# bms-slave-magnetics.net
KiCad netlist of a schematic drawn in Altium Designer
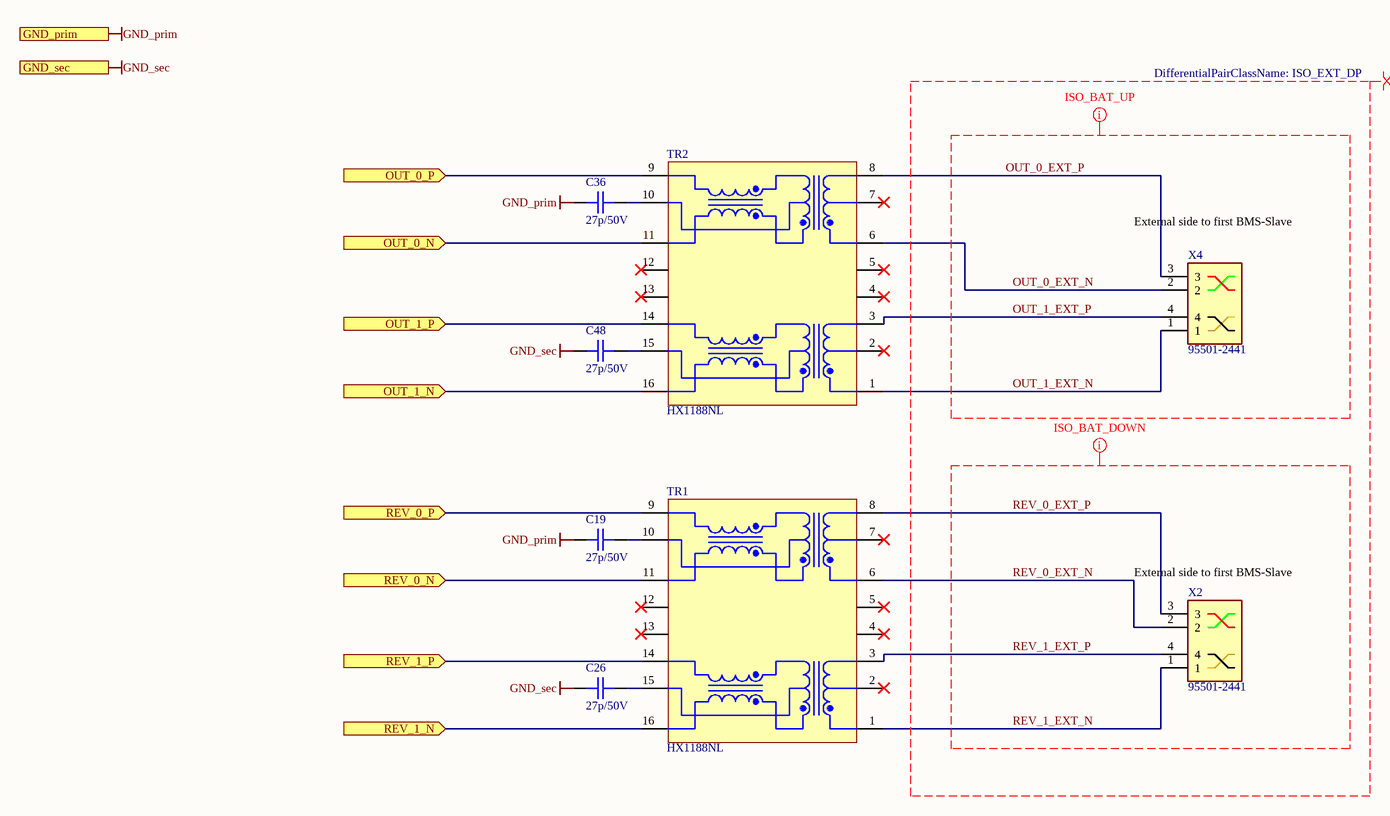
[diagram p0: bms-slave-magnetics.SchDoc]

(export (version "E")
  (design (tool "Eeschema 10.0.6"))
  (components
    (comp (ref "C19")
      (value "27p/50V")
      (footprint "0603C")
      (description "MLCC")
      (fields (field (name "PART NUMBER") "gen_C_ceramic_27p_50V_NP0_0603"))
      (libsource (lib "OE750") (part "C"))
    )
    (comp (ref "C26")
      (value "27p/50V")
      (footprint "0603C")
      (description "MLCC")
      (fields (field (name "PART NUMBER") "gen_C_ceramic_27p_50V_NP0_0603"))
      (libsource (lib "OE750") (part "C"))
    )
    (comp (ref "C36")
      (value "27p/50V")
      (footprint "0603C")
      (description "MLCC")
      (fields (field (name "PART NUMBER") "gen_C_ceramic_27p_50V_NP0_0603"))
      (libsource (lib "OE750") (part "C"))
    )
    (comp (ref "C48")
      (value "27p/50V")
      (footprint "0603C")
      (description "MLCC")
      (fields (field (name "PART NUMBER") "gen_C_ceramic_27p_50V_NP0_0603"))
      (libsource (lib "OE750") (part "C"))
    )
    (comp (ref "TR1")
      (value "HX1188NL")
      (footprint "PULS-MODULE-16_V")
      (fields (field (name "MANUFACTURER") "Pulse Electronics"))
      (libsource (lib "Altium Content Vault") (part "PULS-HX1188NL-MODULE-16"))
    )
    (comp (ref "TR2")
      (value "HX1188NL")
      (footprint "PULS-MODULE-16_V")
      (fields (field (name "MANUFACTURER") "Pulse Electronics"))
      (libsource (lib "Altium Content Vault") (part "PULS-HX1188NL-MODULE-16"))
    )
    (comp (ref "X2")
      (value "95501-2441")
      (footprint "95501-2441")
      (description "Connector")
      (fields (field (name "MOUSER PART NUMBER") "538-95501-2441") (field (name "RS PART NUMBER") "2400913"))
      (libsource (lib "master-010106") (part "95501-2441"))
    )
    (comp (ref "X4")
      (value "95501-2441")
      (footprint "95501-2441")
      (description "Connector")
      (fields (field (name "MOUSER PART NUMBER") "538-95501-2441") (field (name "RS PART NUMBER") "2400913"))
      (libsource (lib "master-010106") (part "95501-2441"))
    )
  )
  (nets
    (net (code "1") (name "/OUT_0_EXT_N") (class "Default")
      (node (ref "TR2") (pin "6") (pinfunction "6_6") (pintype "passive"))
      (node (ref "X4") (pin "2") (pinfunction "2_2") (pintype "passive"))
    )
    (net (code "2") (name "/OUT_0_EXT_P") (class "Default")
      (node (ref "TR2") (pin "8") (pinfunction "8_8") (pintype "passive"))
      (node (ref "X4") (pin "3") (pinfunction "3_3") (pintype "passive"))
    )
    (net (code "3") (name "/OUT_0_N") (class "Default")
      (node (ref "TR2") (pin "11") (pinfunction "11_11") (pintype "passive"))
    )
    (net (code "4") (name "/OUT_0_P") (class "Default")
      (node (ref "TR2") (pin "9") (pinfunction "9_9") (pintype "passive"))
    )
    (net (code "5") (name "/OUT_1_EXT_N") (class "Default")
      (node (ref "TR2") (pin "1") (pinfunction "1_1") (pintype "passive"))
      (node (ref "X4") (pin "1") (pinfunction "1_1") (pintype "passive"))
    )
    (net (code "6") (name "/OUT_1_EXT_P") (class "Default")
      (node (ref "TR2") (pin "3") (pinfunction "3_3") (pintype "passive"))
      (node (ref "X4") (pin "4") (pinfunction "4_4") (pintype "passive"))
    )
    (net (code "7") (name "/OUT_1_N") (class "Default")
      (node (ref "TR2") (pin "16") (pinfunction "16_16") (pintype "passive"))
    )
    (net (code "8") (name "/OUT_1_P") (class "Default")
      (node (ref "TR2") (pin "14") (pinfunction "14_14") (pintype "passive"))
    )
    (net (code "9") (name "/REV_0_EXT_N") (class "Default")
      (node (ref "TR1") (pin "6") (pinfunction "6_6") (pintype "passive"))
      (node (ref "X2") (pin "2") (pinfunction "2_2") (pintype "passive"))
    )
    (net (code "10") (name "/REV_0_EXT_P") (class "Default")
      (node (ref "TR1") (pin "8") (pinfunction "8_8") (pintype "passive"))
      (node (ref "X2") (pin "3") (pinfunction "3_3") (pintype "passive"))
    )
    (net (code "11") (name "/REV_0_N") (class "Default")
      (node (ref "TR1") (pin "11") (pinfunction "11_11") (pintype "passive"))
    )
    (net (code "12") (name "/REV_0_P") (class "Default")
      (node (ref "TR1") (pin "9") (pinfunction "9_9") (pintype "passive"))
    )
    (net (code "13") (name "/REV_1_EXT_N") (class "Default")
      (node (ref "TR1") (pin "1") (pinfunction "1_1") (pintype "passive"))
      (node (ref "X2") (pin "1") (pinfunction "1_1") (pintype "passive"))
    )
    (net (code "14") (name "/REV_1_EXT_P") (class "Default")
      (node (ref "TR1") (pin "3") (pinfunction "3_3") (pintype "passive"))
      (node (ref "X2") (pin "4") (pinfunction "4_4") (pintype "passive"))
    )
    (net (code "15") (name "/REV_1_N") (class "Default")
      (node (ref "TR1") (pin "16") (pinfunction "16_16") (pintype "passive"))
    )
    (net (code "16") (name "/REV_1_P") (class "Default")
      (node (ref "TR1") (pin "14") (pinfunction "14_14") (pintype "passive"))
    )
    (net (code "17") (name "GND_prim") (class "Default")
      (node (ref "C19") (pin "2") (pinfunction "2_2") (pintype "passive"))
      (node (ref "C36") (pin "2") (pinfunction "2_2") (pintype "passive"))
    )
    (net (code "18") (name "GND_sec") (class "Default")
      (node (ref "C26") (pin "1") (pinfunction "1_1") (pintype "passive"))
      (node (ref "C48") (pin "1") (pinfunction "1_1") (pintype "passive"))
    )
    (net (code "19") (name "Net-(C19-Pad1)") (class "Default")
      (node (ref "C19") (pin "1") (pinfunction "1_1") (pintype "passive"))
      (node (ref "TR1") (pin "10") (pinfunction "10_10") (pintype "passive"))
    )
    (net (code "20") (name "Net-(C26-Pad2)") (class "Default")
      (node (ref "C26") (pin "2") (pinfunction "2_2") (pintype "passive"))
      (node (ref "TR1") (pin "15") (pinfunction "15_15") (pintype "passive"))
    )
    (net (code "21") (name "Net-(C36-Pad1)") (class "Default")
      (node (ref "C36") (pin "1") (pinfunction "1_1") (pintype "passive"))
      (node (ref "TR2") (pin "10") (pinfunction "10_10") (pintype "passive"))
    )
    (net (code "22") (name "Net-(C48-Pad2)") (class "Default")
      (node (ref "C48") (pin "2") (pinfunction "2_2") (pintype "passive"))
      (node (ref "TR2") (pin "15") (pinfunction "15_15") (pintype "passive"))
    )
    (net (code "23") (name "unconnected-(TR1-Pad2)") (class "Default")
      (node (ref "TR1") (pin "2") (pinfunction "2_2") (pintype "passive+no_connect"))
    )
    (net (code "24") (name "unconnected-(TR1-Pad4)") (class "Default")
      (node (ref "TR1") (pin "4") (pinfunction "4_4") (pintype "passive+no_connect"))
    )
    (net (code "25") (name "unconnected-(TR1-Pad5)") (class "Default")
      (node (ref "TR1") (pin "5") (pinfunction "5_5") (pintype "passive+no_connect"))
    )
    (net (code "26") (name "unconnected-(TR1-Pad7)") (class "Default")
      (node (ref "TR1") (pin "7") (pinfunction "7_7") (pintype "passive+no_connect"))
    )
    (net (code "27") (name "unconnected-(TR1-Pad12)") (class "Default")
      (node (ref "TR1") (pin "12") (pinfunction "12_12") (pintype "passive+no_connect"))
    )
    (net (code "28") (name "unconnected-(TR1-Pad13)") (class "Default")
      (node (ref "TR1") (pin "13") (pinfunction "13_13") (pintype "passive+no_connect"))
    )
    (net (code "29") (name "unconnected-(TR2-Pad2)") (class "Default")
      (node (ref "TR2") (pin "2") (pinfunction "2_2") (pintype "passive+no_connect"))
    )
    (net (code "30") (name "unconnected-(TR2-Pad4)") (class "Default")
      (node (ref "TR2") (pin "4") (pinfunction "4_4") (pintype "passive+no_connect"))
    )
    (net (code "31") (name "unconnected-(TR2-Pad5)") (class "Default")
      (node (ref "TR2") (pin "5") (pinfunction "5_5") (pintype "passive+no_connect"))
    )
    (net (code "32") (name "unconnected-(TR2-Pad7)") (class "Default")
      (node (ref "TR2") (pin "7") (pinfunction "7_7") (pintype "passive+no_connect"))
    )
    (net (code "33") (name "unconnected-(TR2-Pad12)") (class "Default")
      (node (ref "TR2") (pin "12") (pinfunction "12_12") (pintype "passive+no_connect"))
    )
    (net (code "34") (name "unconnected-(TR2-Pad13)") (class "Default")
      (node (ref "TR2") (pin "13") (pinfunction "13_13") (pintype "passive+no_connect"))
    )
  )
)
